# USBHS_TYPEC.net
KiCad netlist of a schematic drawn in Altium Designer
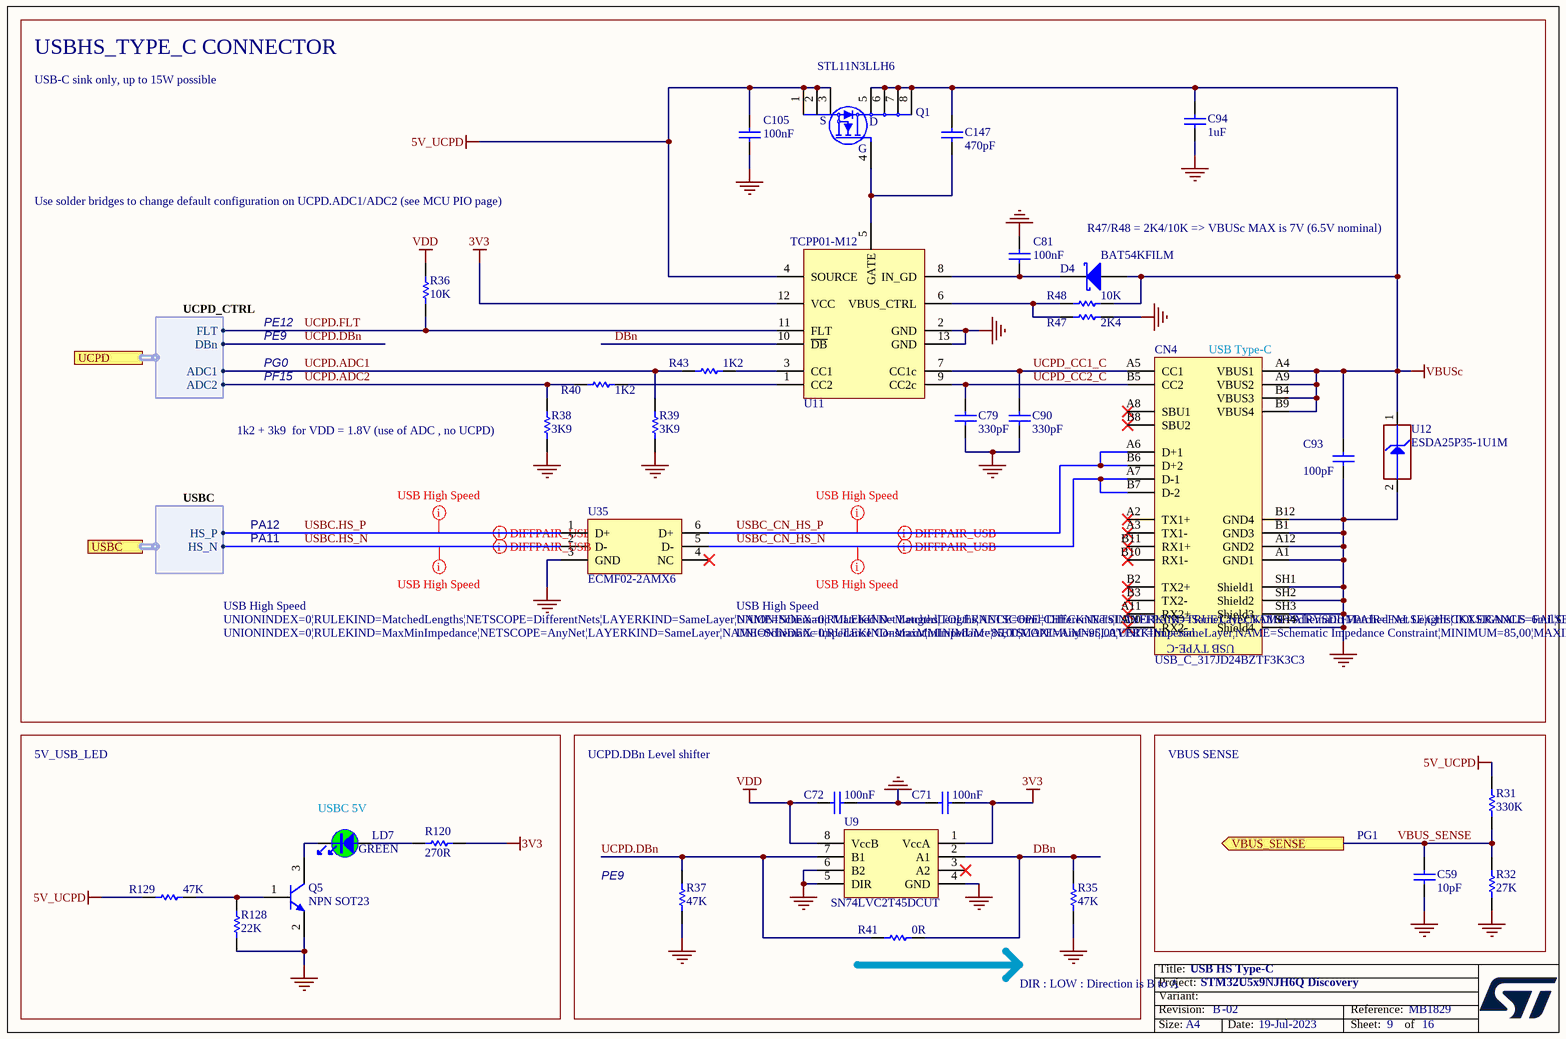
[diagram p0: USBHS_TYPEC.SchDoc]

(export (version "E")
  (design (tool "Eeschema 10.0.6"))
  (components
    (comp (ref "C59")
      (value "10pF")
      (footprint "MCD_PARTS:C0603")
      (description "Capacitor, MLCC, 10pF, 50V, NPO, +/-5%, 0603, T=0.8mm")
      (fields
        (field (name "INTERNAL_PART_NUMBER") "MCD-00637")
        (field (name "MANUFACTURER_PART_NUMBER") "CC0603JRNPO9BN100")
      )
      (libsource (lib "MCD_PARTS_database") (part "Capacitor"))
    )
    (comp (ref "C71")
      (value "100nF")
      (footprint "MCD_PARTS:C0402")
      (description "Capacitor, MLCC, 100nF, 16V, X7R, +/-10%, 0402, T=0.5mm")
      (fields
        (field (name "INTERNAL_PART_NUMBER") "MCD-00006")
        (field (name "MANUFACTURER_PART_NUMBER") "CC0402KRX7R7BB104")
      )
      (libsource (lib "MCD_PARTS_database") (part "Capacitor"))
    )
    (comp (ref "C72")
      (value "100nF")
      (footprint "MCD_PARTS:C0402")
      (description "Capacitor, MLCC, 100nF, 16V, X7R, +/-10%, 0402, T=0.5mm")
      (fields
        (field (name "INTERNAL_PART_NUMBER") "MCD-00006")
        (field (name "MANUFACTURER_PART_NUMBER") "CC0402KRX7R7BB104")
      )
      (libsource (lib "MCD_PARTS_database") (part "Capacitor"))
    )
    (comp (ref "C79")
      (value "330pF")
      (footprint "MCD_PARTS:C0402")
      (description "Capacitor, MLCC, 330pF, 50V, NPO, +/-5%, 0402, T=0.5mm")
      (fields (field (name "INTERNAL_PART_NUMBER") "MCD-01579") (field (name "MANUFACTURER") "YAGEO"))
      (libsource (lib "MCD_PARTS_database") (part "Capacitor"))
    )
    (comp (ref "C81")
      (value "100nF")
      (footprint "MCD_PARTS:C0603")
      (description "Capacitor, MLCC, 100nF, 50V, X7R, +/-10%, 0603, T=0.8mm")
      (fields
        (field (name "INTERNAL_PART_NUMBER") "MCD-01099")
        (field (name "MANUFACTURER_PART_NUMBER") "CC0603KRX7R9BB104")
      )
      (libsource (lib "MCD_PARTS_database") (part "Capacitor"))
    )
    (comp (ref "C90")
      (value "330pF")
      (footprint "MCD_PARTS:C0402")
      (description "Capacitor, MLCC, 330pF, 50V, NPO, +/-5%, 0402, T=0.5mm")
      (fields (field (name "INTERNAL_PART_NUMBER") "MCD-01579") (field (name "MANUFACTURER") "YAGEO"))
      (libsource (lib "MCD_PARTS_database") (part "Capacitor"))
    )
    (comp (ref "C93")
      (value "100pF")
      (footprint "MCD_PARTS:C0402")
      (description "Capacitor, MLCC, 100pF, 50V, NPO, +/-5%, 0402, T=0.5mm")
      (fields (field (name "INTERNAL_PART_NUMBER") "MCD-00205") (field (name "MANUFACTURER") "YAGEO"))
      (libsource (lib "MCD_PARTS_database") (part "Capacitor"))
    )
    (comp (ref "C94")
      (value "1uF")
      (footprint "MCD_PARTS:C0402")
      (description "Capacitor, MLCC, 1uF, 25V, X5R, +/-10%, 0402, T=0.5mm")
      (fields (field (name "INTERNAL_PART_NUMBER") "MCD-02609") (field (name "MANUFACTURER") "YAGEO"))
      (libsource (lib "MCD_PARTS_database") (part "Capacitor"))
    )
    (comp (ref "C105")
      (value "100nF")
      (footprint "MCD_PARTS:C0603")
      (description "Capacitor, MLCC, 100nF, 50V, X7R, +/-10%, 0603, T=0.8mm")
      (fields
        (field (name "INTERNAL_PART_NUMBER") "MCD-01099")
        (field (name "MANUFACTURER_PART_NUMBER") "CC0603KRX7R9BB104")
      )
      (libsource (lib "MCD_PARTS_database") (part "Capacitor"))
    )
    (comp (ref "C147")
      (value "470pF")
      (footprint "MCD_PARTS:C0402")
      (description "Capacitor, MLCC, 470pF, 50V, NPO, +/-5%, 0402, T=0.5mm")
      (fields (field (name "INTERNAL_PART_NUMBER") "MCD-00724") (field (name "MANUFACTURER") "YAGEO"))
      (libsource (lib "MCD_PARTS_database") (part "Capacitor"))
    )
    (comp (ref "CN4")
      (value "USB_C_317JD24BZTF3K3C3")
      (footprint "MCD_PARTS:CON_USB-TYPEC_COXOC_317JD24BZTF3K3C3")
      (description "USB_TypeC, SMD+DIP, T= 2.96mm (for 1.6mm pcb)")
      (fields
        (field (name "INTERNAL_PART_NUMBER") "MCD-01108")
        (field (name "MANUFACTURER_PART_NUMBER") "317JD24BZTF3K3C3")
      )
      (libsource (lib "MCD_PARTS_database") (part "USB_TYPE_C_Receptacle_317JD24BZTF3K3C3"))
    )
    (comp (ref "D4")
      (value "BAT54KFILM")
      (footprint "MCD_PARTS:DIO_SOD523_1A_2K")
      (description "Small signal Schottky diodes")
      (fields
        (field (name "INTERNAL_PART_NUMBER") "MCD-01677")
        (field (name "MANUFACTURER") "STMICROELECTRONICS")
      )
      (libsource (lib "MCD_PARTS_database") (part "SCHOTTKY_1A_2K"))
    )
    (comp (ref "LD7")
      (value "GREEN")
      (footprint "MCD_PARTS:LED_0603_OSRAM_LG-Q396-PS-35_GREEN_1A2K_H0P4")
      (description "LED Green, 0603 SMD, Forward Voltage Typ=2V, Max=2.5V")
      (fields
        (field (name "INTERNAL_PART_NUMBER") "MCD-00588")
        (field (name "MANUFACTURER_PART_NUMBER") "LG Q396-PS-35")
      )
      (libsource (lib "MCD_PARTS_database") (part "LED_green"))
    )
    (comp (ref "Q1")
      (value "STL11N3LLH6")
      (footprint "MCD_PARTS:MOS_POWERFLAT_3P3X3P3_P065")
      (description "N-channel 30 V, 6 mΩ typ, 11 A STripFET™ H6, Power MOSFET in a PowerFLAT™ 3.3x3.3 package")
      (fields (field (name "INTERNAL_PART_NUMBER") "MCD-01810") (field (name "BMS_PART_NUMBER") "9153561"))
      (libsource (lib "MCD_PARTS_database") (part "STL11N3LLH6"))
    )
    (comp (ref "Q5")
      (value "NPN SOT23")
      (footprint "MCD_PARTS:NPN_SOT23")
      (description "NPN Bipolar Transistor")
      (fields
        (field (name "INTERNAL_PART_NUMBER") "MCD-00073")
        (field (name "MANUFACTURER_PART_NUMBER") "BSR14")
      )
      (libsource (lib "MCD_PARTS_database") (part "9013-SOT23"))
    )
    (comp (ref "R31")
      (value "330K")
      (footprint "MCD_PARTS:R0603")
      (description "Resistor, 330K, 0603, +/-1%, 1/10W")
      (fields
        (field (name "INTERNAL_PART_NUMBER") "MCD-00458")
        (field (name "MANUFACTURER_PART_NUMBER") "RC0603FR-07330KL")
      )
      (libsource (lib "MCD_PARTS_database") (part "Resistor"))
    )
    (comp (ref "R32")
      (value "27K")
      (footprint "MCD_PARTS:R0603")
      (description "Resistor, 27K, 0603, +/-1%, 1/10W")
      (fields
        (field (name "INTERNAL_PART_NUMBER") "MCD-00444")
        (field (name "MANUFACTURER_PART_NUMBER") "RC0603FR-0727KL")
      )
      (libsource (lib "MCD_PARTS_database") (part "Resistor"))
    )
    (comp (ref "R35")
      (value "47K")
      (footprint "MCD_PARTS:R0603")
      (description "Resistor, 47K, 0603, 1%, 1/10W")
      (fields (field (name "INTERNAL_PART_NUMBER") "MCD-00222") (field (name "MANUFACTURER") "YAGEO"))
      (libsource (lib "MCD_PARTS_database") (part "Resistor"))
    )
    (comp (ref "R36")
      (value "10K")
      (footprint "MCD_PARTS:R0603")
      (description "Resistor, 10K, 0603, +/-1%, 1/10W")
      (fields
        (field (name "INTERNAL_PART_NUMBER") "MCD-00220")
        (field (name "MANUFACTURER_PART_NUMBER") "RC0603FR-0710KL")
      )
      (libsource (lib "MCD_PARTS_database") (part "Resistor"))
    )
    (comp (ref "R37")
      (value "47K")
      (footprint "MCD_PARTS:R0603")
      (description "Resistor, 47K, 0603, 1%, 1/10W")
      (fields
        (field (name "INTERNAL_PART_NUMBER") "MCD-00222")
        (field (name "MANUFACTURER_PART_NUMBER") "RC0603FR-0747KL")
      )
      (libsource (lib "MCD_PARTS_database") (part "Resistor"))
    )
    (comp (ref "R38")
      (value "3K9")
      (footprint "MCD_PARTS:R0402")
      (description "Resistor, 3K9, 0402, +/-1%, 1/16W, +/-100ppm/°C")
      (fields (field (name "INTERNAL_PART_NUMBER") "MCD-02455") (field (name "MANUFACTURER") "YAGEO"))
      (libsource (lib "MCD_PARTS_database") (part "Resistor"))
    )
    (comp (ref "R39")
      (value "3K9")
      (footprint "MCD_PARTS:R0402")
      (description "Resistor, 3K9, 0402, +/-1%, 1/16W, +/-100ppm/°C")
      (fields (field (name "INTERNAL_PART_NUMBER") "MCD-02455") (field (name "MANUFACTURER") "YAGEO"))
      (libsource (lib "MCD_PARTS_database") (part "Resistor"))
    )
    (comp (ref "R40")
      (value "1K2")
      (footprint "MCD_PARTS:R0402")
      (description "Resistor, 1K2, 0402, +/-1%, 1/16W")
      (fields (field (name "INTERNAL_PART_NUMBER") "MCD-00373") (field (name "MANUFACTURER") "YAGEO"))
      (libsource (lib "MCD_PARTS_database") (part "Resistor"))
    )
    (comp (ref "R41")
      (value "0R")
      (footprint "MCD_PARTS:R0402")
      (description "Resistor, 0R, 0402, +/-5%, 1/16W")
      (fields
        (field (name "INTERNAL_PART_NUMBER") "MCD-00052")
        (field (name "MANUFACTURER_PART_NUMBER") "RC0402JR-070RL")
      )
      (libsource (lib "MCD_PARTS_database") (part "Resistor"))
    )
    (comp (ref "R43")
      (value "1K2")
      (footprint "MCD_PARTS:R0402")
      (description "Resistor, 1K2, 0402, +/-1%, 1/16W")
      (fields (field (name "INTERNAL_PART_NUMBER") "MCD-00373") (field (name "MANUFACTURER") "YAGEO"))
      (libsource (lib "MCD_PARTS_database") (part "Resistor"))
    )
    (comp (ref "R47")
      (value "2K4")
      (footprint "MCD_PARTS:R0402")
      (description "Resistor, 2K4, 0402, +/-1%, 1/16W")
      (fields (field (name "INTERNAL_PART_NUMBER") "MCD-00433") (field (name "MANUFACTURER") "YAGEO"))
      (libsource (lib "MCD_PARTS_database") (part "Resistor"))
    )
    (comp (ref "R48")
      (value "10K")
      (footprint "MCD_PARTS:R0402")
      (description "Resistor, 10K, 0402, +/-1%, 1/16W")
      (fields (field (name "INTERNAL_PART_NUMBER") "MCD-00053") (field (name "BMS_PART_NUMBER") "9131590"))
      (libsource (lib "MCD_PARTS_database") (part "Resistor"))
    )
    (comp (ref "R120")
      (value "270R")
      (footprint "MCD_PARTS:R0402")
      (description "Resistor, 270R, 0402, +/-1%, 1/16W")
      (fields (field (name "INTERNAL_PART_NUMBER") "MCD-00441") (field (name "MANUFACTURER") "YAGEO"))
      (libsource (lib "MCD_PARTS_database") (part "Resistor"))
    )
    (comp (ref "R128")
      (value "22K")
      (footprint "MCD_PARTS:R0603")
      (description "Resistor, 22K, 0603, +/-1%, 1/10W")
      (fields
        (field (name "INTERNAL_PART_NUMBER") "MCD-00430")
        (field (name "MANUFACTURER_PART_NUMBER") "RC0603FR-0722KL")
      )
      (libsource (lib "MCD_PARTS_database") (part "Resistor"))
    )
    (comp (ref "R129")
      (value "47K")
      (footprint "MCD_PARTS:R0603")
      (description "Resistor, 47K, 0603, 1%, 1/10W")
      (fields
        (field (name "INTERNAL_PART_NUMBER") "MCD-00222")
        (field (name "MANUFACTURER_PART_NUMBER") "RC0603FR-0747KL")
      )
      (libsource (lib "MCD_PARTS_database") (part "Resistor"))
    )
    (comp (ref "U9")
      (value "SN74LVC2T45DCUT")
      (footprint "MCD_PARTS:ICC_VSSOP8_DCU_R-PDSO-G8_2X2P30_P050")
      (description "Dual bit dual supply bus transceiver")
      (fields
        (field (name "INTERNAL_PART_NUMBER") "MCD-00264")
        (field (name "MANUFACTURER") "TEXAS INSTRUMENTS")
      )
      (libsource (lib "MCD_PARTS_database") (part "SN74LVC2T45DCUT"))
    )
    (comp (ref "U11")
      (value "TCPP01-M12")
      (footprint "MCD_PARTS:ICC_QFN12L-EPAD_3X3_P050")
      (description "USB Type-C Port Protection for USB Power Delivery, PPS compliant")
      (fields
        (field (name "INTERNAL_PART_NUMBER") "MCD-01809")
        (field (name "MANUFACTURER") "STMICROELECTRONICS")
      )
      (libsource (lib "MCD_PARTS_database") (part "TCPP01-M12"))
    )
    (comp (ref "U12")
      (value "ESDA25P35-1U1M")
      (footprint "MCD_PARTS:ESD_QFN1610_2N_1K_2A")
      (description "High power Transient voltage suppressor:25V/35A EOS and ESD transients protection.")
      (fields
        (field (name "INTERNAL_PART_NUMBER") "MCD-01207")
        (field (name "MANUFACTURER") "STMICROELECTRONICS")
      )
      (libsource (lib "MCD_PARTS_database") (part "ESD-TRANSIL"))
    )
    (comp (ref "U35")
      (value "ECMF02-2AMX6")
      (footprint "MCD_PARTS:ESD_QFN-6L_1P7X1P5_P050")
      (description "Common mode filter with ESD protection for USB 2.0 interface")
      (fields
        (field (name "INTERNAL_PART_NUMBER") "MCD-00649")
        (field (name "MANUFACTURER") "STMICROELECTRONICS")
      )
      (libsource (lib "MCD_PARTS_database") (part "ECMF02-2AMX6"))
    )
  )
  (nets
    (net (code "3") (name "/DBn") (class "Default")
      (node (ref "R35") (pin "2") (pinfunction "2_2") (pintype "passive"))
      (node (ref "R41") (pin "2") (pinfunction "2_2") (pintype "passive"))
      (node (ref "U11") (pin "10") (pinfunction "~{DB}_10") (pintype "passive"))
      (node (ref "U9") (pin "2") (pinfunction "A1_2") (pintype "passive"))
    )
    (net (code "4") (name "/UCPD.ADC1") (class "Default")
      (node (ref "R39") (pin "2") (pinfunction "2_2") (pintype "passive"))
      (node (ref "R43") (pin "1") (pinfunction "1_1") (pintype "passive"))
    )
    (net (code "5") (name "/UCPD.ADC2") (class "Default")
      (node (ref "R38") (pin "2") (pinfunction "2_2") (pintype "passive"))
      (node (ref "R40") (pin "1") (pinfunction "1_1") (pintype "passive"))
    )
    (net (code "6") (name "/UCPD.DBn") (class "Default")
      (node (ref "R37") (pin "1") (pinfunction "1_1") (pintype "passive"))
      (node (ref "R41") (pin "1") (pinfunction "1_1") (pintype "passive"))
      (node (ref "U9") (pin "7") (pinfunction "B1_7") (pintype "passive"))
    )
    (net (code "7") (name "/UCPD.FLT") (class "Default")
      (node (ref "R36") (pin "1") (pinfunction "1_1") (pintype "passive"))
      (node (ref "U11") (pin "11") (pinfunction "FLT_11") (pintype "passive"))
    )
    (net (code "8") (name "/UCPD_CC1_C") (class "Default")
      (node (ref "C90") (pin "2") (pinfunction "2_2") (pintype "passive"))
      (node (ref "CN4") (pin "A5") (pinfunction "CC1_A5") (pintype "passive"))
      (node (ref "U11") (pin "7") (pinfunction "CC1c_7") (pintype "passive"))
    )
    (net (code "9") (name "/UCPD_CC2_C") (class "Default")
      (node (ref "C79") (pin "2") (pinfunction "2_2") (pintype "passive"))
      (node (ref "CN4") (pin "B5") (pinfunction "CC2_B5") (pintype "passive"))
      (node (ref "U11") (pin "9") (pinfunction "CC2c_9") (pintype "passive"))
    )
    (net (code "10") (name "/USBC.HS_N") (class "Default")
      (node (ref "U35") (pin "2") (pinfunction "D-_2") (pintype "passive"))
    )
    (net (code "11") (name "/USBC.HS_P") (class "Default")
      (node (ref "U35") (pin "1") (pinfunction "D+_1") (pintype "passive"))
    )
    (net (code "12") (name "/USBC_CN_HS_N") (class "Default")
      (node (ref "CN4") (pin "A7") (pinfunction "D-1_A7") (pintype "passive"))
      (node (ref "CN4") (pin "B7") (pinfunction "D-2_B7") (pintype "passive"))
      (node (ref "U35") (pin "5") (pinfunction "D-_5") (pintype "passive"))
    )
    (net (code "13") (name "/USBC_CN_HS_P") (class "Default")
      (node (ref "CN4") (pin "A6") (pinfunction "D+1_A6") (pintype "passive"))
      (node (ref "CN4") (pin "B6") (pinfunction "D+2_B6") (pintype "passive"))
      (node (ref "U35") (pin "6") (pinfunction "D+_6") (pintype "passive"))
    )
    (net (code "14") (name "/VBUS_SENSE") (class "Default")
      (node (ref "C59") (pin "2") (pinfunction "2_2") (pintype "passive"))
      (node (ref "R31") (pin "1") (pinfunction "1_1") (pintype "passive"))
      (node (ref "R32") (pin "2") (pinfunction "2_2") (pintype "passive"))
    )
    (net (code "17") (name "3V3") (class "Default")
      (node (ref "C71") (pin "2") (pinfunction "2_2") (pintype "passive"))
      (node (ref "R120") (pin "2") (pinfunction "2_2") (pintype "passive"))
      (node (ref "U11") (pin "12") (pinfunction "VCC_12") (pintype "passive"))
      (node (ref "U9") (pin "1") (pinfunction "VccA_1") (pintype "power_in"))
    )
    (net (code "18") (name "5V_UCPD") (class "Default")
      (node (ref "C105") (pin "1") (pinfunction "1_1") (pintype "passive"))
      (node (ref "Q1") (pin "1") (pinfunction "S_1") (pintype "passive"))
      (node (ref "Q1") (pin "2") (pinfunction "S_2") (pintype "passive"))
      (node (ref "Q1") (pin "3") (pinfunction "S_3") (pintype "passive"))
      (node (ref "R129") (pin "1") (pinfunction "1_1") (pintype "passive"))
      (node (ref "R31") (pin "2") (pinfunction "2_2") (pintype "passive"))
      (node (ref "U11") (pin "4") (pinfunction "SOURCE_4") (pintype "passive"))
    )
    (net (code "19") (name "GND") (class "Default")
      (node (ref "C105") (pin "2") (pinfunction "2_2") (pintype "passive"))
      (node (ref "C59") (pin "1") (pinfunction "1_1") (pintype "passive"))
      (node (ref "C71") (pin "1") (pinfunction "1_1") (pintype "passive"))
      (node (ref "C72") (pin "2") (pinfunction "2_2") (pintype "passive"))
      (node (ref "C79") (pin "1") (pinfunction "1_1") (pintype "passive"))
      (node (ref "C81") (pin "1") (pinfunction "1_1") (pintype "passive"))
      (node (ref "C90") (pin "1") (pinfunction "1_1") (pintype "passive"))
      (node (ref "C93") (pin "1") (pinfunction "1_1") (pintype "passive"))
      (node (ref "C94") (pin "1") (pinfunction "1_1") (pintype "passive"))
      (node (ref "CN4") (pin "A1") (pinfunction "GND1_A1") (pintype "passive"))
      (node (ref "CN4") (pin "A12") (pinfunction "GND2_A12") (pintype "passive"))
      (node (ref "CN4") (pin "B1") (pinfunction "GND3_B1") (pintype "passive"))
      (node (ref "CN4") (pin "B12") (pinfunction "GND4_B12") (pintype "passive"))
      (node (ref "CN4") (pin "SH1") (pinfunction "Shield1_SH1") (pintype "passive"))
      (node (ref "CN4") (pin "SH2") (pinfunction "Shield2_SH2") (pintype "passive"))
      (node (ref "CN4") (pin "SH3") (pinfunction "Shield3_SH3") (pintype "passive"))
      (node (ref "CN4") (pin "SH4") (pinfunction "Shield4_SH4") (pintype "passive"))
      (node (ref "Q5") (pin "2") (pinfunction "E_2") (pintype "passive"))
      (node (ref "R128") (pin "1") (pinfunction "1_1") (pintype "passive"))
      (node (ref "R32") (pin "1") (pinfunction "1_1") (pintype "passive"))
      (node (ref "R35") (pin "1") (pinfunction "1_1") (pintype "passive"))
      (node (ref "R37") (pin "2") (pinfunction "2_2") (pintype "passive"))
      (node (ref "R38") (pin "1") (pinfunction "1_1") (pintype "passive"))
      (node (ref "R39") (pin "1") (pinfunction "1_1") (pintype "passive"))
      (node (ref "R47") (pin "2") (pinfunction "2_2") (pintype "passive"))
      (node (ref "U11") (pin "13") (pinfunction "GND_13") (pintype "passive"))
      (node (ref "U11") (pin "2") (pinfunction "GND_2") (pintype "passive"))
      (node (ref "U12") (pin "2") (pinfunction "GND_2") (pintype "passive"))
      (node (ref "U35") (pin "3") (pinfunction "GND_3") (pintype "passive"))
      (node (ref "U9") (pin "4") (pinfunction "GND_4") (pintype "power_in"))
      (node (ref "U9") (pin "5") (pinfunction "DIR_5") (pintype "passive"))
      (node (ref "U9") (pin "6") (pinfunction "B2_6") (pintype "passive"))
    )
    (net (code "20") (name "Net-(D4-K)") (class "Default")
      (node (ref "C81") (pin "2") (pinfunction "2_2") (pintype "passive"))
      (node (ref "D4") (pin "2") (pinfunction "K_2") (pintype "passive"))
      (node (ref "U11") (pin "8") (pinfunction "IN_GD_8") (pintype "passive"))
    )
    (net (code "21") (name "Net-(LD7-Pad1)") (class "Default")
      (node (ref "LD7") (pin "1") (pintype "passive"))
      (node (ref "R120") (pin "1") (pinfunction "1_1") (pintype "passive"))
    )
    (net (code "22") (name "Net-(Q1-G)") (class "Default")
      (node (ref "C147") (pin "1") (pinfunction "1_1") (pintype "passive"))
      (node (ref "Q1") (pin "4") (pinfunction "G_4") (pintype "passive"))
      (node (ref "U11") (pin "5") (pinfunction "GATE_5") (pintype "passive"))
    )
    (net (code "23") (name "Net-(Q5-B)") (class "Default")
      (node (ref "Q5") (pin "1") (pinfunction "B_1") (pintype "passive"))
      (node (ref "R128") (pin "2") (pinfunction "2_2") (pintype "passive"))
      (node (ref "R129") (pin "2") (pinfunction "2_2") (pintype "passive"))
    )
    (net (code "24") (name "Net-(Q5-C)") (class "Default")
      (node (ref "LD7") (pin "2") (pintype "passive"))
      (node (ref "Q5") (pin "3") (pinfunction "C_3") (pintype "passive"))
    )
    (net (code "25") (name "Net-(U11-CC1)") (class "Default")
      (node (ref "R43") (pin "2") (pinfunction "2_2") (pintype "passive"))
      (node (ref "U11") (pin "3") (pinfunction "CC1_3") (pintype "passive"))
    )
    (net (code "26") (name "Net-(U11-CC2)") (class "Default")
      (node (ref "R40") (pin "2") (pinfunction "2_2") (pintype "passive"))
      (node (ref "U11") (pin "1") (pinfunction "CC2_1") (pintype "passive"))
    )
    (net (code "27") (name "Net-(U11-VBUS_CTRL)") (class "Default")
      (node (ref "R47") (pin "1") (pinfunction "1_1") (pintype "passive"))
      (node (ref "R48") (pin "1") (pinfunction "1_1") (pintype "passive"))
      (node (ref "U11") (pin "6") (pinfunction "VBUS_CTRL_6") (pintype "passive"))
    )
    (net (code "28") (name "VBUSc") (class "Default")
      (node (ref "C147") (pin "2") (pinfunction "2_2") (pintype "passive"))
      (node (ref "C93") (pin "2") (pinfunction "2_2") (pintype "passive"))
      (node (ref "C94") (pin "2") (pinfunction "2_2") (pintype "passive"))
      (node (ref "CN4") (pin "A4") (pinfunction "VBUS1_A4") (pintype "passive"))
      (node (ref "CN4") (pin "A9") (pinfunction "VBUS2_A9") (pintype "passive"))
      (node (ref "CN4") (pin "B4") (pinfunction "VBUS3_B4") (pintype "passive"))
      (node (ref "CN4") (pin "B9") (pinfunction "VBUS4_B9") (pintype "passive"))
      (node (ref "D4") (pin "1") (pinfunction "A_1") (pintype "passive"))
      (node (ref "Q1") (pin "5") (pinfunction "D_5") (pintype "passive"))
      (node (ref "Q1") (pin "6") (pinfunction "D_6") (pintype "passive"))
      (node (ref "Q1") (pin "7") (pinfunction "D_7") (pintype "passive"))
      (node (ref "Q1") (pin "8") (pinfunction "D_8") (pintype "passive"))
      (node (ref "R48") (pin "2") (pinfunction "2_2") (pintype "passive"))
      (node (ref "U12") (pin "1") (pinfunction "IO1_1") (pintype "passive"))
    )
    (net (code "29") (name "VDD") (class "Default")
      (node (ref "C72") (pin "1") (pinfunction "1_1") (pintype "passive"))
      (node (ref "R36") (pin "2") (pinfunction "2_2") (pintype "passive"))
      (node (ref "U9") (pin "8") (pinfunction "VccB_8") (pintype "power_in"))
    )
    (net (code "30") (name "unconnected-(CN4-RX1+-PadB11)") (class "Default")
      (node (ref "CN4") (pin "B11") (pinfunction "RX1+_B11") (pintype "passive+no_connect"))
    )
    (net (code "31") (name "unconnected-(CN4-RX1--PadB10)") (class "Default")
      (node (ref "CN4") (pin "B10") (pinfunction "RX1-_B10") (pintype "passive+no_connect"))
    )
    (net (code "32") (name "unconnected-(CN4-RX2+-PadA11)") (class "Default")
      (node (ref "CN4") (pin "A11") (pinfunction "RX2+_A11") (pintype "passive+no_connect"))
    )
    (net (code "33") (name "unconnected-(CN4-RX2--PadA10)") (class "Default")
      (node (ref "CN4") (pin "A10") (pinfunction "RX2-_A10") (pintype "passive+no_connect"))
    )
    (net (code "34") (name "unconnected-(CN4-SBU1-PadA8)") (class "Default")
      (node (ref "CN4") (pin "A8") (pinfunction "SBU1_A8") (pintype "passive+no_connect"))
    )
    (net (code "35") (name "unconnected-(CN4-SBU2-PadB8)") (class "Default")
      (node (ref "CN4") (pin "B8") (pinfunction "SBU2_B8") (pintype "passive+no_connect"))
    )
    (net (code "36") (name "unconnected-(CN4-TX1+-PadA2)") (class "Default")
      (node (ref "CN4") (pin "A2") (pinfunction "TX1+_A2") (pintype "passive+no_connect"))
    )
    (net (code "37") (name "unconnected-(CN4-TX1--PadA3)") (class "Default")
      (node (ref "CN4") (pin "A3") (pinfunction "TX1-_A3") (pintype "passive+no_connect"))
    )
    (net (code "38") (name "unconnected-(CN4-TX2+-PadB2)") (class "Default")
      (node (ref "CN4") (pin "B2") (pinfunction "TX2+_B2") (pintype "passive+no_connect"))
    )
    (net (code "39") (name "unconnected-(CN4-TX2--PadB3)") (class "Default")
      (node (ref "CN4") (pin "B3") (pinfunction "TX2-_B3") (pintype "passive+no_connect"))
    )
    (net (code "40") (name "unconnected-(U9-A2-Pad3)") (class "Default")
      (node (ref "U9") (pin "3") (pinfunction "A2_3") (pintype "passive+no_connect"))
    )
    (net (code "41") (name "unconnected-(U35-NC-Pad4)") (class "Default")
      (node (ref "U35") (pin "4") (pinfunction "NC_4") (pintype "passive+no_connect"))
    )
  )
)
